# beaglebone-cape.net
KiCad netlist of a schematic drawn in EAGLE
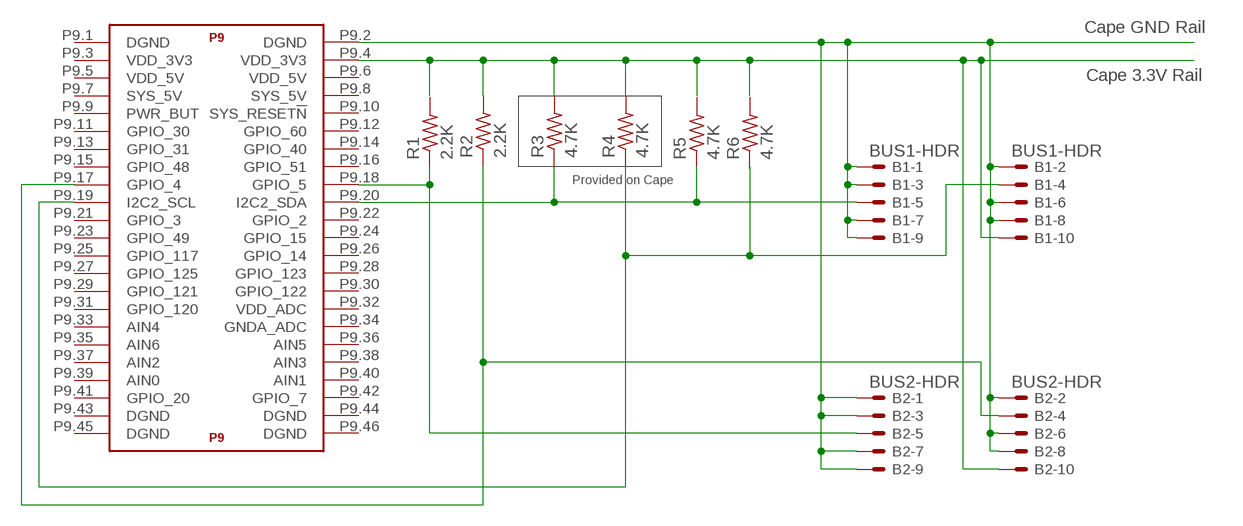
[diagram p0: schematic, sheet 1]

(export (version "E")
  (design (tool "Eeschema 10.0.6"))
  (components
    (comp (ref "B1")
      (value "BUS1-HDR")
      (footprint "eagle-import:87758-1016")
      (fields (field (name "MF") "MOLEX") (field (name "MPN") "87758-1016") (field (name "MPN_1") "BUS1-HDR"))
      (libsource (lib "eagle-import") (part "87758-1016"))
    )
    (comp (ref "B2")
      (value "BUS2-HDR")
      (footprint "eagle-import:87758-1016")
      (fields (field (name "MF") "MOLEX") (field (name "MPN") "87758-1016") (field (name "MPN_1") "BUS2-HDR"))
      (libsource (lib "eagle-import") (part "87758-1016"))
    )
    (comp (ref "R1")
      (value "2.2K")
      (footprint "eagle-import:0207_15")
      (libsource (lib "eagle-import") (part "R-US_0207/15"))
    )
    (comp (ref "R2")
      (value "2.2K")
      (footprint "eagle-import:0207_15")
      (libsource (lib "eagle-import") (part "R-US_0207/15"))
    )
    (comp (ref "R3")
      (value "4.7K")
      (footprint "eagle-import:0207_15")
      (libsource (lib "eagle-import") (part "R-US_0207/15"))
    )
    (comp (ref "R4")
      (value "4.7K")
      (footprint "eagle-import:0207_15")
      (libsource (lib "eagle-import") (part "R-US_0207/15"))
    )
    (comp (ref "R5")
      (value "4.7K")
      (footprint "eagle-import:0207_15")
      (libsource (lib "eagle-import") (part "R-US_0207/15"))
    )
    (comp (ref "R6")
      (value "4.7K")
      (footprint "eagle-import:0207_15")
      (libsource (lib "eagle-import") (part "R-US_0207/15"))
    )
    (comp (ref "U$6")
      (value "BEAGLE_BONE_BLACK_CAPE")
      (footprint "eagle-import:BEAGLE_BONE_BLACK_CAPE")
      (libsource (lib "eagle-import") (part "BEAGLE_BONE_BLACK_CAPE"))
    )
  )
  (nets
    (net (code "1") (name "Net-(B1A-S)") (class "Default")
      (node (ref "B1") (pin "1") (pinfunction "S_1") (pintype "passive"))
      (node (ref "B1") (pin "2") (pinfunction "S_2") (pintype "passive"))
      (node (ref "B1") (pin "3") (pinfunction "S_3") (pintype "passive"))
      (node (ref "B1") (pin "6") (pinfunction "S_6") (pintype "passive"))
      (node (ref "B1") (pin "7") (pinfunction "S_7") (pintype "passive"))
      (node (ref "B1") (pin "8") (pinfunction "S_8") (pintype "passive"))
      (node (ref "B1") (pin "9") (pinfunction "S_9") (pintype "passive"))
      (node (ref "B2") (pin "1") (pinfunction "S_1") (pintype "passive"))
      (node (ref "B2") (pin "2") (pinfunction "S_2") (pintype "passive"))
      (node (ref "B2") (pin "3") (pinfunction "S_3") (pintype "passive"))
      (node (ref "B2") (pin "6") (pinfunction "S_6") (pintype "passive"))
      (node (ref "B2") (pin "7") (pinfunction "S_7") (pintype "passive"))
      (node (ref "B2") (pin "8") (pinfunction "S_8") (pintype "passive"))
      (node (ref "B2") (pin "9") (pinfunction "S_9") (pintype "passive"))
      (node (ref "U$6") (pin "P9.2") (pinfunction "DGND_P9.2") (pintype "bidirectional"))
    )
    (net (code "2") (name "Net-(B1B-S)") (class "Default")
      (node (ref "B1") (pin "10") (pinfunction "S_10") (pintype "passive"))
      (node (ref "B2") (pin "10") (pinfunction "S_10") (pintype "passive"))
      (node (ref "R2") (pin "2") (pinfunction "2_2") (pintype "passive"))
      (node (ref "R3") (pin "2") (pinfunction "2_2") (pintype "passive"))
      (node (ref "R4") (pin "2") (pinfunction "2_2") (pintype "passive"))
      (node (ref "U$6") (pin "P9.4") (pinfunction "VDD_3V3_P9.4") (pintype "bidirectional"))
    )
    (net (code "3") (name "Net-(B1E-S)") (class "Default")
      (node (ref "B1") (pin "4") (pinfunction "S_4") (pintype "passive"))
      (node (ref "R4") (pin "1") (pinfunction "1_1") (pintype "passive"))
      (node (ref "U$6") (pin "P9.19") (pinfunction "I2C2_SCL_P9.19") (pintype "bidirectional"))
    )
    (net (code "4") (name "Net-(B1F-S)") (class "Default")
      (node (ref "B1") (pin "5") (pinfunction "S_5") (pintype "passive"))
      (node (ref "R3") (pin "1") (pinfunction "1_1") (pintype "passive"))
      (node (ref "U$6") (pin "P9.20") (pinfunction "I2C2_SDA_P9.20") (pintype "bidirectional"))
    )
    (net (code "5") (name "Net-(B2E-S)") (class "Default")
      (node (ref "B2") (pin "4") (pinfunction "S_4") (pintype "passive"))
      (node (ref "R2") (pin "1") (pinfunction "1_1") (pintype "passive"))
      (node (ref "U$6") (pin "P9.17") (pinfunction "GPIO_4_P9.17") (pintype "bidirectional"))
    )
    (net (code "6") (name "Net-(B2F-S)") (class "Default")
      (node (ref "B2") (pin "5") (pinfunction "S_5") (pintype "passive"))
      (node (ref "U$6") (pin "P9.18") (pinfunction "GPIO_5_P9.18") (pintype "bidirectional"))
    )
    (net (code "7") (name "unconnected-(R1-Pad1)") (class "Default")
      (node (ref "R1") (pin "1") (pinfunction "1_1") (pintype "passive"))
    )
    (net (code "8") (name "unconnected-(R1-Pad2)") (class "Default")
      (node (ref "R1") (pin "2") (pinfunction "2_2") (pintype "passive"))
    )
    (net (code "9") (name "unconnected-(R5-Pad1)") (class "Default")
      (node (ref "R5") (pin "1") (pinfunction "1_1") (pintype "passive"))
    )
    (net (code "10") (name "unconnected-(R5-Pad2)") (class "Default")
      (node (ref "R5") (pin "2") (pinfunction "2_2") (pintype "passive"))
    )
    (net (code "11") (name "unconnected-(R6-Pad1)") (class "Default")
      (node (ref "R6") (pin "1") (pinfunction "1_1") (pintype "passive"))
    )
    (net (code "12") (name "unconnected-(R6-Pad2)") (class "Default")
      (node (ref "R6") (pin "2") (pinfunction "2_2") (pintype "passive"))
    )
    (net (code "13") (name "unconnected-(U$6B-AIN0-PadP9.39)") (class "Default")
      (node (ref "U$6") (pin "P9.39") (pinfunction "AIN0_P9.39") (pintype "bidirectional"))
    )
    (net (code "14") (name "unconnected-(U$6B-AIN1-PadP9.40)") (class "Default")
      (node (ref "U$6") (pin "P9.40") (pinfunction "AIN1_P9.40") (pintype "bidirectional"))
    )
    (net (code "15") (name "unconnected-(U$6B-AIN2-PadP9.37)") (class "Default")
      (node (ref "U$6") (pin "P9.37") (pinfunction "AIN2_P9.37") (pintype "bidirectional"))
    )
    (net (code "16") (name "unconnected-(U$6B-AIN3-PadP9.38)") (class "Default")
      (node (ref "U$6") (pin "P9.38") (pinfunction "AIN3_P9.38") (pintype "bidirectional"))
    )
    (net (code "17") (name "unconnected-(U$6B-AIN4-PadP9.33)") (class "Default")
      (node (ref "U$6") (pin "P9.33") (pinfunction "AIN4_P9.33") (pintype "bidirectional"))
    )
    (net (code "18") (name "unconnected-(U$6B-AIN5-PadP9.36)") (class "Default")
      (node (ref "U$6") (pin "P9.36") (pinfunction "AIN5_P9.36") (pintype "bidirectional"))
    )
    (net (code "19") (name "unconnected-(U$6B-AIN6-PadP9.35)") (class "Default")
      (node (ref "U$6") (pin "P9.35") (pinfunction "AIN6_P9.35") (pintype "bidirectional"))
    )
    (net (code "20") (name "unconnected-(U$6B-DGND-PadP9.1)") (class "Default")
      (node (ref "U$6") (pin "P9.1") (pinfunction "DGND_P9.1") (pintype "bidirectional"))
    )
    (net (code "21") (name "unconnected-(U$6B-DGND-PadP9.43)") (class "Default")
      (node (ref "U$6") (pin "P9.43") (pinfunction "DGND_P9.43") (pintype "bidirectional"))
    )
    (net (code "22") (name "unconnected-(U$6B-DGND-PadP9.44)") (class "Default")
      (node (ref "U$6") (pin "P9.44") (pinfunction "DGND_P9.44") (pintype "bidirectional"))
    )
    (net (code "23") (name "unconnected-(U$6B-DGND-PadP9.45)") (class "Default")
      (node (ref "U$6") (pin "P9.45") (pinfunction "DGND_P9.45") (pintype "bidirectional"))
    )
    (net (code "24") (name "unconnected-(U$6B-DGND-PadP9.46)") (class "Default")
      (node (ref "U$6") (pin "P9.46") (pinfunction "DGND_P9.46") (pintype "bidirectional"))
    )
    (net (code "25") (name "unconnected-(U$6B-GNDA_ADC-PadP9.34)") (class "Default")
      (node (ref "U$6") (pin "P9.34") (pinfunction "GNDA_ADC_P9.34") (pintype "bidirectional"))
    )
    (net (code "26") (name "unconnected-(U$6B-GPIO_2-PadP9.22)") (class "Default")
      (node (ref "U$6") (pin "P9.22") (pinfunction "GPIO_2_P9.22") (pintype "bidirectional"))
    )
    (net (code "27") (name "unconnected-(U$6B-GPIO_3-PadP9.21)") (class "Default")
      (node (ref "U$6") (pin "P9.21") (pinfunction "GPIO_3_P9.21") (pintype "bidirectional"))
    )
    (net (code "28") (name "unconnected-(U$6B-GPIO_7-PadP9.42)") (class "Default")
      (node (ref "U$6") (pin "P9.42") (pinfunction "GPIO_7_P9.42") (pintype "bidirectional"))
    )
    (net (code "29") (name "unconnected-(U$6B-GPIO_14-PadP9.26)") (class "Default")
      (node (ref "U$6") (pin "P9.26") (pinfunction "GPIO_14_P9.26") (pintype "bidirectional"))
    )
    (net (code "30") (name "unconnected-(U$6B-GPIO_15-PadP9.24)") (class "Default")
      (node (ref "U$6") (pin "P9.24") (pinfunction "GPIO_15_P9.24") (pintype "bidirectional"))
    )
    (net (code "31") (name "unconnected-(U$6B-GPIO_20-PadP9.41)") (class "Default")
      (node (ref "U$6") (pin "P9.41") (pinfunction "GPIO_20_P9.41") (pintype "bidirectional"))
    )
    (net (code "32") (name "unconnected-(U$6B-GPIO_30-PadP9.11)") (class "Default")
      (node (ref "U$6") (pin "P9.11") (pinfunction "GPIO_30_P9.11") (pintype "bidirectional"))
    )
    (net (code "33") (name "unconnected-(U$6B-GPIO_31-PadP9.13)") (class "Default")
      (node (ref "U$6") (pin "P9.13") (pinfunction "GPIO_31_P9.13") (pintype "bidirectional"))
    )
    (net (code "34") (name "unconnected-(U$6B-GPIO_40-PadP9.14)") (class "Default")
      (node (ref "U$6") (pin "P9.14") (pinfunction "GPIO_40_P9.14") (pintype "bidirectional"))
    )
    (net (code "35") (name "unconnected-(U$6B-GPIO_48-PadP9.15)") (class "Default")
      (node (ref "U$6") (pin "P9.15") (pinfunction "GPIO_48_P9.15") (pintype "bidirectional"))
    )
    (net (code "36") (name "unconnected-(U$6B-GPIO_49-PadP9.23)") (class "Default")
      (node (ref "U$6") (pin "P9.23") (pinfunction "GPIO_49_P9.23") (pintype "bidirectional"))
    )
    (net (code "37") (name "unconnected-(U$6B-GPIO_51-PadP9.16)") (class "Default")
      (node (ref "U$6") (pin "P9.16") (pinfunction "GPIO_51_P9.16") (pintype "bidirectional"))
    )
    (net (code "38") (name "unconnected-(U$6B-GPIO_60-PadP9.12)") (class "Default")
      (node (ref "U$6") (pin "P9.12") (pinfunction "GPIO_60_P9.12") (pintype "bidirectional"))
    )
    (net (code "39") (name "unconnected-(U$6B-GPIO_117-PadP9.25)") (class "Default")
      (node (ref "U$6") (pin "P9.25") (pinfunction "GPIO_117_P9.25") (pintype "bidirectional"))
    )
    (net (code "40") (name "unconnected-(U$6B-GPIO_120-PadP9.31)") (class "Default")
      (node (ref "U$6") (pin "P9.31") (pinfunction "GPIO_120_P9.31") (pintype "bidirectional"))
    )
    (net (code "41") (name "unconnected-(U$6B-GPIO_121-PadP9.29)") (class "Default")
      (node (ref "U$6") (pin "P9.29") (pinfunction "GPIO_121_P9.29") (pintype "bidirectional"))
    )
    (net (code "42") (name "unconnected-(U$6B-GPIO_122-PadP9.30)") (class "Default")
      (node (ref "U$6") (pin "P9.30") (pinfunction "GPIO_122_P9.30") (pintype "bidirectional"))
    )
    (net (code "43") (name "unconnected-(U$6B-GPIO_123-PadP9.28)") (class "Default")
      (node (ref "U$6") (pin "P9.28") (pinfunction "GPIO_123_P9.28") (pintype "bidirectional"))
    )
    (net (code "44") (name "unconnected-(U$6B-GPIO_125-PadP9.27)") (class "Default")
      (node (ref "U$6") (pin "P9.27") (pinfunction "GPIO_125_P9.27") (pintype "bidirectional"))
    )
    (net (code "45") (name "unconnected-(U$6B-PWR_BUT-PadP9.9)") (class "Default")
      (node (ref "U$6") (pin "P9.9") (pinfunction "PWR_BUT_P9.9") (pintype "bidirectional"))
    )
    (net (code "46") (name "unconnected-(U$6B-SYS_5V-PadP9.7)") (class "Default")
      (node (ref "U$6") (pin "P9.7") (pinfunction "SYS_5V_P9.7") (pintype "bidirectional"))
    )
    (net (code "47") (name "unconnected-(U$6B-SYS_5V-PadP9.8)") (class "Default")
      (node (ref "U$6") (pin "P9.8") (pinfunction "SYS_5V_P9.8") (pintype "bidirectional"))
    )
    (net (code "48") (name "unconnected-(U$6B-SYS_RESET~{N}-PadP9.10)") (class "Default")
      (node (ref "U$6") (pin "P9.10") (pinfunction "SYS_RESET~{N}_P9.10") (pintype "bidirectional"))
    )
    (net (code "49") (name "unconnected-(U$6B-VDD_3V3-PadP9.3)") (class "Default")
      (node (ref "U$6") (pin "P9.3") (pinfunction "VDD_3V3_P9.3") (pintype "bidirectional"))
    )
    (net (code "50") (name "unconnected-(U$6B-VDD_5V-PadP9.5)") (class "Default")
      (node (ref "U$6") (pin "P9.5") (pinfunction "VDD_5V_P9.5") (pintype "bidirectional"))
    )
    (net (code "51") (name "unconnected-(U$6B-VDD_5V-PadP9.6)") (class "Default")
      (node (ref "U$6") (pin "P9.6") (pinfunction "VDD_5V_P9.6") (pintype "bidirectional"))
    )
    (net (code "52") (name "unconnected-(U$6B-VDD_ADC-PadP9.32)") (class "Default")
      (node (ref "U$6") (pin "P9.32") (pinfunction "VDD_ADC_P9.32") (pintype "bidirectional"))
    )
  )
)
